# patch-panel.net
KiCad netlist of a schematic drawn in EAGLE
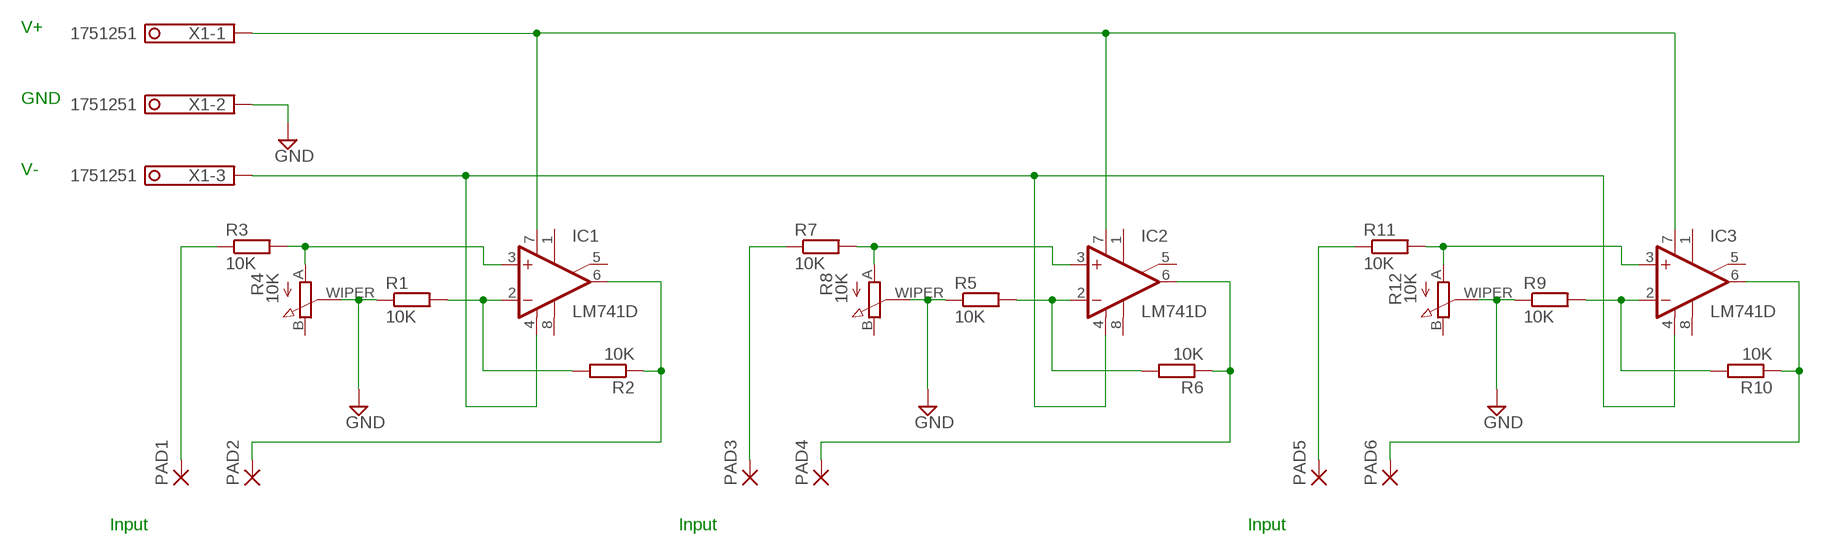
[diagram p0: schematic, sheet 1]

(export (version "E")
  (design (tool "Eeschema 10.0.6"))
  (components
    (comp (ref "IC1")
      (value "LM741D")
      (footprint "eagle-import:SO08")
      (libsource (lib "eagle-import") (part "741DLM"))
    )
    (comp (ref "IC2")
      (value "LM741D")
      (footprint "eagle-import:SO08")
      (libsource (lib "eagle-import") (part "741DLM"))
    )
    (comp (ref "IC3")
      (value "LM741D")
      (footprint "eagle-import:SO08")
      (libsource (lib "eagle-import") (part "741DLM"))
    )
    (comp (ref "PAD1")
      (value "2,54/1,0")
      (footprint "eagle-import:2,54_1,0")
      (libsource (lib "eagle-import") (part "2,54/1,0"))
    )
    (comp (ref "PAD2")
      (value "2,54/1,0")
      (footprint "eagle-import:2,54_1,0")
      (libsource (lib "eagle-import") (part "2,54/1,0"))
    )
    (comp (ref "PAD3")
      (value "2,54/1,0")
      (footprint "eagle-import:2,54_1,0")
      (libsource (lib "eagle-import") (part "2,54/1,0"))
    )
    (comp (ref "PAD4")
      (value "2,54/1,0")
      (footprint "eagle-import:2,54_1,0")
      (libsource (lib "eagle-import") (part "2,54/1,0"))
    )
    (comp (ref "PAD5")
      (value "2,54/1,0")
      (footprint "eagle-import:2,54_1,0")
      (libsource (lib "eagle-import") (part "2,54/1,0"))
    )
    (comp (ref "PAD6")
      (value "2,54/1,0")
      (footprint "eagle-import:2,54_1,0")
      (libsource (lib "eagle-import") (part "2,54/1,0"))
    )
    (comp (ref "R1")
      (value "10K")
      (footprint "eagle-import:M1206")
      (libsource (lib "eagle-import") (part "R-EU_M1206"))
    )
    (comp (ref "R2")
      (value "10K")
      (footprint "eagle-import:M1206")
      (libsource (lib "eagle-import") (part "R-EU_M1206"))
    )
    (comp (ref "R3")
      (value "10K")
      (footprint "eagle-import:M1206")
      (libsource (lib "eagle-import") (part "R-EU_M1206"))
    )
    (comp (ref "R4")
      (value "10K")
      (footprint "eagle-import:PTVA09A-4")
      (libsource (lib "eagle-import") (part "PTVA09A-4"))
    )
    (comp (ref "R5")
      (value "10K")
      (footprint "eagle-import:M1206")
      (libsource (lib "eagle-import") (part "R-EU_M1206"))
    )
    (comp (ref "R6")
      (value "10K")
      (footprint "eagle-import:M1206")
      (libsource (lib "eagle-import") (part "R-EU_M1206"))
    )
    (comp (ref "R7")
      (value "10K")
      (footprint "eagle-import:M1206")
      (libsource (lib "eagle-import") (part "R-EU_M1206"))
    )
    (comp (ref "R8")
      (value "10K")
      (footprint "eagle-import:PTVA09A-4")
      (libsource (lib "eagle-import") (part "PTVA09A-4"))
    )
    (comp (ref "R9")
      (value "10K")
      (footprint "eagle-import:M1206")
      (libsource (lib "eagle-import") (part "R-EU_M1206"))
    )
    (comp (ref "R10")
      (value "10K")
      (footprint "eagle-import:M1206")
      (libsource (lib "eagle-import") (part "R-EU_M1206"))
    )
    (comp (ref "R11")
      (value "10K")
      (footprint "eagle-import:M1206")
      (libsource (lib "eagle-import") (part "R-EU_M1206"))
    )
    (comp (ref "R12")
      (value "10K")
      (footprint "eagle-import:PTVA09A-4")
      (libsource (lib "eagle-import") (part "PTVA09A-4"))
    )
    (comp (ref "X1")
      (value "1751251")
      (footprint "eagle-import:1751251")
      (libsource (lib "eagle-import") (part "1751251"))
    )
  )
  (nets
    (net (code "1") (name "GND") (class "Default")
      (node (ref "R1") (pin "1") (pinfunction "1_1") (pintype "passive"))
      (node (ref "R12") (pin "WIPER") (pinfunction "WIPER_WIPER") (pintype "passive"))
      (node (ref "R4") (pin "WIPER") (pinfunction "WIPER_WIPER") (pintype "passive"))
      (node (ref "R5") (pin "1") (pinfunction "1_1") (pintype "passive"))
      (node (ref "R8") (pin "WIPER") (pinfunction "WIPER_WIPER") (pintype "passive"))
      (node (ref "R9") (pin "1") (pinfunction "1_1") (pintype "passive"))
      (node (ref "X1") (pin "2") (pinfunction "K_2") (pintype "passive"))
    )
    (net (code "2") (name "Net-(IC1-+IN)") (class "Default")
      (node (ref "IC1") (pin "3") (pinfunction "+IN_3") (pintype "input"))
      (node (ref "R3") (pin "2") (pinfunction "2_2") (pintype "passive"))
      (node (ref "R4") (pin "A") (pinfunction "A_A") (pintype "passive"))
    )
    (net (code "3") (name "Net-(IC1--IN)") (class "Default")
      (node (ref "IC1") (pin "2") (pinfunction "-IN_2") (pintype "input"))
      (node (ref "R1") (pin "2") (pinfunction "2_2") (pintype "passive"))
      (node (ref "R2") (pin "2") (pinfunction "2_2") (pintype "passive"))
    )
    (net (code "4") (name "Net-(IC1-OUT)") (class "Default")
      (node (ref "IC1") (pin "6") (pinfunction "OUT_6") (pintype "output"))
      (node (ref "PAD2") (pin "1") (pinfunction "P_1") (pintype "passive"))
      (node (ref "R2") (pin "1") (pinfunction "1_1") (pintype "passive"))
    )
    (net (code "5") (name "Net-(IC1-V+)") (class "Default")
      (node (ref "IC1") (pin "7") (pinfunction "V+_7") (pintype "power_in"))
      (node (ref "IC2") (pin "7") (pinfunction "V+_7") (pintype "power_in"))
      (node (ref "IC3") (pin "7") (pinfunction "V+_7") (pintype "power_in"))
      (node (ref "X1") (pin "1") (pinfunction "K_1") (pintype "passive"))
    )
    (net (code "6") (name "Net-(IC1-V-)") (class "Default")
      (node (ref "IC1") (pin "4") (pinfunction "V-_4") (pintype "power_in"))
      (node (ref "IC2") (pin "4") (pinfunction "V-_4") (pintype "power_in"))
      (node (ref "IC3") (pin "4") (pinfunction "V-_4") (pintype "power_in"))
      (node (ref "X1") (pin "3") (pinfunction "K_3") (pintype "passive"))
    )
    (net (code "7") (name "Net-(IC2-+IN)") (class "Default")
      (node (ref "IC2") (pin "3") (pinfunction "+IN_3") (pintype "input"))
      (node (ref "R7") (pin "2") (pinfunction "2_2") (pintype "passive"))
      (node (ref "R8") (pin "A") (pinfunction "A_A") (pintype "passive"))
    )
    (net (code "8") (name "Net-(IC2--IN)") (class "Default")
      (node (ref "IC2") (pin "2") (pinfunction "-IN_2") (pintype "input"))
      (node (ref "R5") (pin "2") (pinfunction "2_2") (pintype "passive"))
      (node (ref "R6") (pin "2") (pinfunction "2_2") (pintype "passive"))
    )
    (net (code "9") (name "Net-(IC2-OUT)") (class "Default")
      (node (ref "IC2") (pin "6") (pinfunction "OUT_6") (pintype "output"))
      (node (ref "PAD4") (pin "1") (pinfunction "P_1") (pintype "passive"))
      (node (ref "R6") (pin "1") (pinfunction "1_1") (pintype "passive"))
    )
    (net (code "10") (name "Net-(IC3-+IN)") (class "Default")
      (node (ref "IC3") (pin "3") (pinfunction "+IN_3") (pintype "input"))
      (node (ref "R11") (pin "2") (pinfunction "2_2") (pintype "passive"))
      (node (ref "R12") (pin "A") (pinfunction "A_A") (pintype "passive"))
    )
    (net (code "11") (name "Net-(IC3--IN)") (class "Default")
      (node (ref "IC3") (pin "2") (pinfunction "-IN_2") (pintype "input"))
      (node (ref "R10") (pin "2") (pinfunction "2_2") (pintype "passive"))
      (node (ref "R9") (pin "2") (pinfunction "2_2") (pintype "passive"))
    )
    (net (code "12") (name "Net-(IC3-OUT)") (class "Default")
      (node (ref "IC3") (pin "6") (pinfunction "OUT_6") (pintype "output"))
      (node (ref "PAD6") (pin "1") (pinfunction "P_1") (pintype "passive"))
      (node (ref "R10") (pin "1") (pinfunction "1_1") (pintype "passive"))
    )
    (net (code "13") (name "Net-(PAD1-P)") (class "Default")
      (node (ref "PAD1") (pin "1") (pinfunction "P_1") (pintype "passive"))
      (node (ref "R3") (pin "1") (pinfunction "1_1") (pintype "passive"))
    )
    (net (code "14") (name "Net-(PAD3-P)") (class "Default")
      (node (ref "PAD3") (pin "1") (pinfunction "P_1") (pintype "passive"))
      (node (ref "R7") (pin "1") (pinfunction "1_1") (pintype "passive"))
    )
    (net (code "15") (name "Net-(PAD5-P)") (class "Default")
      (node (ref "PAD5") (pin "1") (pinfunction "P_1") (pintype "passive"))
      (node (ref "R11") (pin "1") (pinfunction "1_1") (pintype "passive"))
    )
    (net (code "16") (name "unconnected-(IC1-ON1-Pad1)") (class "Default")
      (node (ref "IC1") (pin "1") (pinfunction "ON1_1") (pintype "passive"))
    )
    (net (code "17") (name "unconnected-(IC1-ON2-Pad5)") (class "Default")
      (node (ref "IC1") (pin "5") (pinfunction "ON2_5") (pintype "passive"))
    )
    (net (code "18") (name "unconnected-(IC1-OPT-Pad8)") (class "Default")
      (node (ref "IC1") (pin "8") (pinfunction "OPT_8") (pintype "passive"))
    )
    (net (code "19") (name "unconnected-(IC2-ON1-Pad1)") (class "Default")
      (node (ref "IC2") (pin "1") (pinfunction "ON1_1") (pintype "passive"))
    )
    (net (code "20") (name "unconnected-(IC2-ON2-Pad5)") (class "Default")
      (node (ref "IC2") (pin "5") (pinfunction "ON2_5") (pintype "passive"))
    )
    (net (code "21") (name "unconnected-(IC2-OPT-Pad8)") (class "Default")
      (node (ref "IC2") (pin "8") (pinfunction "OPT_8") (pintype "passive"))
    )
    (net (code "22") (name "unconnected-(IC3-ON1-Pad1)") (class "Default")
      (node (ref "IC3") (pin "1") (pinfunction "ON1_1") (pintype "passive"))
    )
    (net (code "23") (name "unconnected-(IC3-ON2-Pad5)") (class "Default")
      (node (ref "IC3") (pin "5") (pinfunction "ON2_5") (pintype "passive"))
    )
    (net (code "24") (name "unconnected-(IC3-OPT-Pad8)") (class "Default")
      (node (ref "IC3") (pin "8") (pinfunction "OPT_8") (pintype "passive"))
    )
    (net (code "25") (name "unconnected-(R4-PadB)") (class "Default")
      (node (ref "R4") (pin "B") (pinfunction "B_B") (pintype "passive"))
    )
    (net (code "26") (name "unconnected-(R8-PadB)") (class "Default")
      (node (ref "R8") (pin "B") (pinfunction "B_B") (pintype "passive"))
    )
    (net (code "27") (name "unconnected-(R12-PadB)") (class "Default")
      (node (ref "R12") (pin "B") (pinfunction "B_B") (pintype "passive"))
    )
  )
)
